# Sheet1.net
KiCad netlist of a schematic drawn in Altium Designer
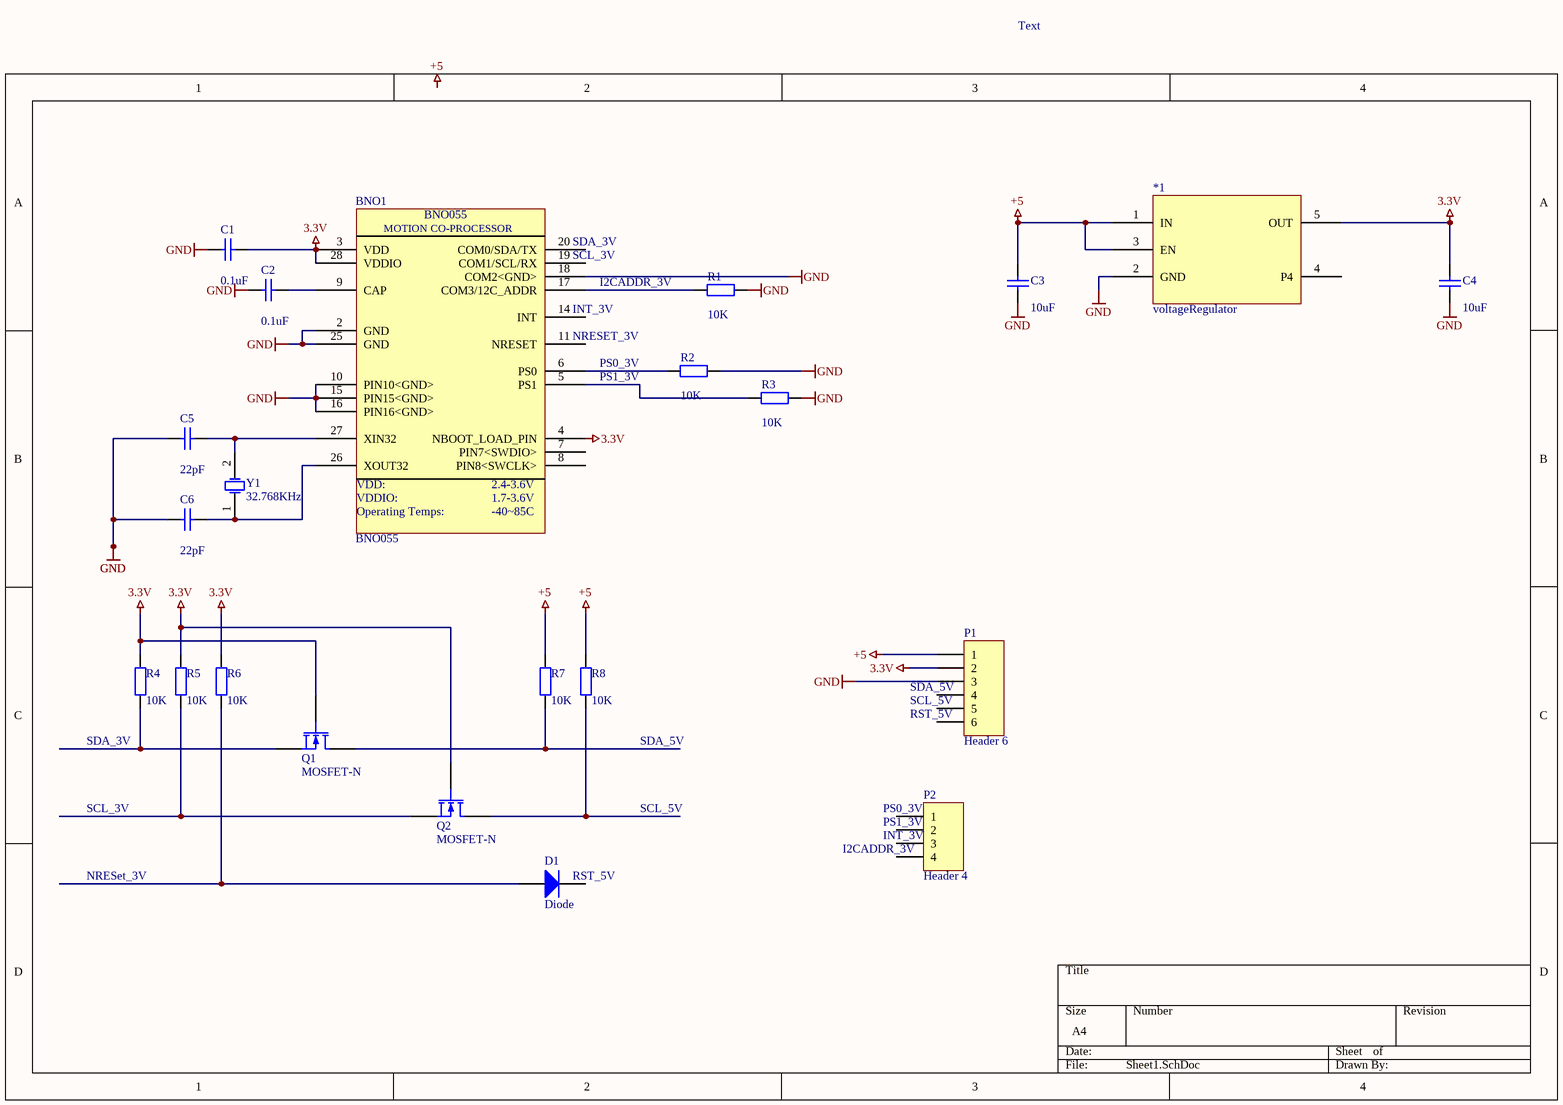
[diagram p0: Sheet1.SchDoc]

(export (version "E")
  (design (tool "Eeschema 10.0.6"))
  (components
    (comp (ref "*1")
      (value "voltageRegulator")
      (footprint "SOT95P245X110-5N")
      (libsource (lib "BNO055SCHEMATIC") (part "voltageRegulator"))
    )
    (comp (ref "BNO1")
      (value "BNO055")
      (footprint "SOIC127P980X95_HS-22N")
      (libsource (lib "BNO055SCHEMATIC") (part "BNO055"))
    )
    (comp (ref "C1")
      (value "0.1uF")
      (footprint "RAD-0.3")
      (description "Capacitor")
      (fields (field (name "PUBLISHER") "Altium Limited"))
      (libsource (lib "Miscellaneous Devices") (part "Cap"))
    )
    (comp (ref "C2")
      (value "0.1uF")
      (footprint "RAD-0.3")
      (description "Capacitor")
      (fields (field (name "PUBLISHER") "Altium Limited"))
      (libsource (lib "Miscellaneous Devices") (part "Cap"))
    )
    (comp (ref "C3")
      (value "10uF")
      (footprint "RAD-0.3")
      (description "Capacitor")
      (fields (field (name "PUBLISHER") "Altium Limited"))
      (libsource (lib "Miscellaneous Devices") (part "Cap"))
    )
    (comp (ref "C4")
      (value "10uF")
      (footprint "RAD-0.3")
      (description "Capacitor")
      (fields (field (name "PUBLISHER") "Altium Limited"))
      (libsource (lib "Miscellaneous Devices") (part "Cap"))
    )
    (comp (ref "C5")
      (value "22pF")
      (footprint "RAD-0.3")
      (description "Capacitor")
      (fields (field (name "PUBLISHER") "Altium Limited"))
      (libsource (lib "Miscellaneous Devices") (part "Cap"))
    )
    (comp (ref "C6")
      (value "22pF")
      (footprint "RAD-0.3")
      (description "Capacitor")
      (fields (field (name "PUBLISHER") "Altium Limited"))
      (libsource (lib "Miscellaneous Devices") (part "Cap"))
    )
    (comp (ref "D1")
      (value "Diode")
      (footprint "SMC")
      (description "Default Diode")
      (fields (field (name "PUBLISHER") "Altium Limited"))
      (libsource (lib "Miscellaneous Devices") (part "Diode"))
    )
    (comp (ref "P1")
      (value "Header 6")
      (footprint "HDR1X6")
      (description "Header, 6-Pin")
      (fields (field (name "PUBLISHER") "Altium Limited"))
      (libsource (lib "Miscellaneous Connectors") (part "Header 6"))
    )
    (comp (ref "P2")
      (value "Header 4")
      (footprint "HDR1X4")
      (description "Header, 4-Pin")
      (fields (field (name "PUBLISHER") "Altium Limited"))
      (libsource (lib "Miscellaneous Connectors") (part "Header 4"))
    )
    (comp (ref "Q1")
      (value "MOSFET-N")
      (footprint "E3")
      (description "N-Channel MOSFET")
      (fields (field (name "PUBLISHER") "Altium Limited"))
      (libsource (lib "Miscellaneous Devices") (part "MOSFET-N"))
    )
    (comp (ref "Q2")
      (value "MOSFET-N")
      (footprint "E3")
      (description "N-Channel MOSFET")
      (fields (field (name "PUBLISHER") "Altium Limited"))
      (libsource (lib "Miscellaneous Devices") (part "MOSFET-N"))
    )
    (comp (ref "R1")
      (value "10K")
      (footprint "AXIAL-0.4")
      (description "Resistor")
      (fields (field (name "PUBLISHER") "Altium Limited"))
      (libsource (lib "") (part "Res2_1"))
    )
    (comp (ref "R2")
      (value "10K")
      (footprint "AXIAL-0.4")
      (description "Resistor")
      (fields (field (name "PUBLISHER") "Altium Limited"))
      (libsource (lib "") (part "Res2_1"))
    )
    (comp (ref "R3")
      (value "10K")
      (footprint "AXIAL-0.4")
      (description "Resistor")
      (fields (field (name "PUBLISHER") "Altium Limited"))
      (libsource (lib "") (part "Res2_1"))
    )
    (comp (ref "R4")
      (value "10K")
      (footprint "AXIAL-0.4")
      (description "Resistor")
      (fields (field (name "PUBLISHER") "Altium Limited"))
      (libsource (lib "Miscellaneous Devices") (part "Res2"))
    )
    (comp (ref "R5")
      (value "10K")
      (footprint "AXIAL-0.4")
      (description "Resistor")
      (fields (field (name "PUBLISHER") "Altium Limited"))
      (libsource (lib "Miscellaneous Devices") (part "Res2"))
    )
    (comp (ref "R6")
      (value "10K")
      (footprint "AXIAL-0.4")
      (description "Resistor")
      (fields (field (name "PUBLISHER") "Altium Limited"))
      (libsource (lib "Miscellaneous Devices") (part "Res2"))
    )
    (comp (ref "R7")
      (value "10K")
      (footprint "AXIAL-0.4")
      (description "Resistor")
      (fields (field (name "PUBLISHER") "Altium Limited"))
      (libsource (lib "Miscellaneous Devices") (part "Res2"))
    )
    (comp (ref "R8")
      (value "10K")
      (footprint "AXIAL-0.4")
      (description "Resistor")
      (fields (field (name "PUBLISHER") "Altium Limited"))
      (libsource (lib "Miscellaneous Devices") (part "Res2"))
    )
    (comp (ref "Y1")
      (value "32.768KHz")
      (footprint "R38")
      (description "Crystal Oscillator")
      (fields (field (name "PUBLISHER") "Altium Limited"))
      (libsource (lib "Miscellaneous Devices") (part "XTAL"))
    )
  )
  (nets
    (net (code "1") (name "+5") (class "Default")
      (node (ref "*1") (pin "1") (pinfunction "IN_1") (pintype "passive"))
      (node (ref "*1") (pin "3") (pinfunction "EN_3") (pintype "passive"))
      (node (ref "C3") (pin "2") (pinfunction "2_2") (pintype "passive"))
      (node (ref "P1") (pin "1") (pinfunction "1_1") (pintype "passive"))
      (node (ref "R7") (pin "2") (pinfunction "2_2") (pintype "passive"))
      (node (ref "R8") (pin "2") (pinfunction "2_2") (pintype "passive"))
    )
    (net (code "2") (name "3.3V") (class "Default")
      (node (ref "*1") (pin "5") (pinfunction "OUT_5") (pintype "passive"))
      (node (ref "BNO1") (pin "28") (pinfunction "VDDIO_28") (pintype "passive"))
      (node (ref "BNO1") (pin "3") (pinfunction "VDD_3") (pintype "passive"))
      (node (ref "BNO1") (pin "4") (pinfunction "NBOOT_LOAD_PIN_4") (pintype "passive"))
      (node (ref "C1") (pin "2") (pinfunction "2_2") (pintype "passive"))
      (node (ref "C4") (pin "2") (pinfunction "2_2") (pintype "passive"))
      (node (ref "P1") (pin "2") (pinfunction "2_2") (pintype "passive"))
      (node (ref "Q1") (pin "2") (pinfunction "G_2") (pintype "passive"))
      (node (ref "Q2") (pin "2") (pinfunction "G_2") (pintype "passive"))
      (node (ref "R4") (pin "2") (pinfunction "2_2") (pintype "passive"))
      (node (ref "R5") (pin "2") (pinfunction "2_2") (pintype "passive"))
      (node (ref "R6") (pin "2") (pinfunction "2_2") (pintype "passive"))
    )
    (net (code "3") (name "GND") (class "Default")
      (node (ref "*1") (pin "2") (pinfunction "GND_2") (pintype "passive"))
      (node (ref "BNO1") (pin "10") (pinfunction "PIN10<GND>_10") (pintype "passive"))
      (node (ref "BNO1") (pin "15") (pinfunction "PIN15<GND>_15") (pintype "passive"))
      (node (ref "BNO1") (pin "16") (pinfunction "PIN16<GND>_16") (pintype "passive"))
      (node (ref "BNO1") (pin "18") (pinfunction "COM2<GND>_18") (pintype "passive"))
      (node (ref "BNO1") (pin "2") (pinfunction "GND_2") (pintype "passive"))
      (node (ref "BNO1") (pin "25") (pinfunction "GND_25") (pintype "passive"))
      (node (ref "C1") (pin "1") (pinfunction "1_1") (pintype "passive"))
      (node (ref "C2") (pin "1") (pinfunction "1_1") (pintype "passive"))
      (node (ref "C3") (pin "1") (pinfunction "1_1") (pintype "passive"))
      (node (ref "C4") (pin "1") (pinfunction "1_1") (pintype "passive"))
      (node (ref "C5") (pin "1") (pinfunction "1_1") (pintype "passive"))
      (node (ref "C6") (pin "1") (pinfunction "1_1") (pintype "passive"))
      (node (ref "P1") (pin "3") (pinfunction "3_3") (pintype "passive"))
      (node (ref "R1") (pin "1") (pinfunction "1_1") (pintype "passive"))
      (node (ref "R2") (pin "1") (pinfunction "1_1") (pintype "passive"))
      (node (ref "R3") (pin "1") (pinfunction "1_1") (pintype "passive"))
    )
    (net (code "4") (name "Net-(BNO1-CAP)") (class "Default")
      (node (ref "BNO1") (pin "9") (pinfunction "CAP_9") (pintype "passive"))
      (node (ref "C2") (pin "2") (pinfunction "2_2") (pintype "passive"))
    )
    (net (code "5") (name "Net-(BNO1-COM3{slash}12C_ADDR)") (class "Default")
      (node (ref "BNO1") (pin "17") (pinfunction "COM3/12C_ADDR_17") (pintype "passive"))
      (node (ref "R1") (pin "2") (pinfunction "2_2") (pintype "passive"))
    )
    (net (code "6") (name "Net-(BNO1-PS0)") (class "Default")
      (node (ref "BNO1") (pin "6") (pinfunction "PS0_6") (pintype "passive"))
      (node (ref "R2") (pin "2") (pinfunction "2_2") (pintype "passive"))
    )
    (net (code "7") (name "Net-(BNO1-PS1)") (class "Default")
      (node (ref "BNO1") (pin "5") (pinfunction "PS1_5") (pintype "passive"))
      (node (ref "R3") (pin "2") (pinfunction "2_2") (pintype "passive"))
    )
    (net (code "8") (name "Net-(BNO1-XIN32)") (class "Default")
      (node (ref "BNO1") (pin "27") (pinfunction "XIN32_27") (pintype "passive"))
      (node (ref "C5") (pin "2") (pinfunction "2_2") (pintype "passive"))
      (node (ref "Y1") (pin "2") (pinfunction "OSC2_2") (pintype "passive"))
    )
    (net (code "9") (name "Net-(BNO1-XOUT32)") (class "Default")
      (node (ref "BNO1") (pin "26") (pinfunction "XOUT32_26") (pintype "passive"))
      (node (ref "C6") (pin "2") (pinfunction "2_2") (pintype "passive"))
      (node (ref "Y1") (pin "1") (pinfunction "OSC1_1") (pintype "passive"))
    )
    (net (code "10") (name "Net-(D1-A)") (class "Default")
      (node (ref "D1") (pin "1") (pinfunction "A_1") (pintype "passive"))
      (node (ref "R6") (pin "1") (pinfunction "1_1") (pintype "passive"))
    )
    (net (code "11") (name "Net-(Q1-D)") (class "Default")
      (node (ref "Q1") (pin "1") (pinfunction "D_1") (pintype "passive"))
      (node (ref "R7") (pin "1") (pinfunction "1_1") (pintype "passive"))
    )
    (net (code "12") (name "Net-(Q1-S)") (class "Default")
      (node (ref "Q1") (pin "3") (pinfunction "S_3") (pintype "passive"))
      (node (ref "R4") (pin "1") (pinfunction "1_1") (pintype "passive"))
    )
    (net (code "13") (name "Net-(Q2-D)") (class "Default")
      (node (ref "Q2") (pin "1") (pinfunction "D_1") (pintype "passive"))
      (node (ref "R8") (pin "1") (pinfunction "1_1") (pintype "passive"))
    )
    (net (code "14") (name "Net-(Q2-S)") (class "Default")
      (node (ref "Q2") (pin "3") (pinfunction "S_3") (pintype "passive"))
      (node (ref "R5") (pin "1") (pinfunction "1_1") (pintype "passive"))
    )
    (net (code "15") (name "unconnected-(*1-P4-Pad4)") (class "Default")
      (node (ref "*1") (pin "4") (pinfunction "P4_4") (pintype "passive"))
    )
    (net (code "16") (name "unconnected-(BNO1-COM0{slash}SDA{slash}TX-Pad20)") (class "Default")
      (node (ref "BNO1") (pin "20") (pinfunction "COM0/SDA/TX_20") (pintype "passive"))
    )
    (net (code "17") (name "unconnected-(BNO1-COM1{slash}SCL{slash}RX-Pad19)") (class "Default")
      (node (ref "BNO1") (pin "19") (pinfunction "COM1/SCL/RX_19") (pintype "passive"))
    )
    (net (code "18") (name "unconnected-(BNO1-INT-Pad14)") (class "Default")
      (node (ref "BNO1") (pin "14") (pinfunction "INT_14") (pintype "passive"))
    )
    (net (code "19") (name "unconnected-(BNO1-NRESET-Pad11)") (class "Default")
      (node (ref "BNO1") (pin "11") (pinfunction "NRESET_11") (pintype "passive"))
    )
    (net (code "20") (name "unconnected-(BNO1-PIN7<SWDIO>-Pad7)") (class "Default")
      (node (ref "BNO1") (pin "7") (pinfunction "PIN7<SWDIO>_7") (pintype "passive"))
    )
    (net (code "21") (name "unconnected-(BNO1-PIN8<SWCLK>-Pad8)") (class "Default")
      (node (ref "BNO1") (pin "8") (pinfunction "PIN8<SWCLK>_8") (pintype "passive"))
    )
    (net (code "22") (name "unconnected-(D1-K-Pad2)") (class "Default")
      (node (ref "D1") (pin "2") (pinfunction "K_2") (pintype "passive"))
    )
    (net (code "23") (name "unconnected-(P1-Pad4)") (class "Default")
      (node (ref "P1") (pin "4") (pinfunction "4_4") (pintype "passive"))
    )
    (net (code "24") (name "unconnected-(P1-Pad5)") (class "Default")
      (node (ref "P1") (pin "5") (pinfunction "5_5") (pintype "passive"))
    )
    (net (code "25") (name "unconnected-(P1-Pad6)") (class "Default")
      (node (ref "P1") (pin "6") (pinfunction "6_6") (pintype "passive"))
    )
    (net (code "26") (name "unconnected-(P2-Pad1)") (class "Default")
      (node (ref "P2") (pin "1") (pinfunction "1_1") (pintype "passive"))
    )
    (net (code "27") (name "unconnected-(P2-Pad2)") (class "Default")
      (node (ref "P2") (pin "2") (pinfunction "2_2") (pintype "passive"))
    )
    (net (code "28") (name "unconnected-(P2-Pad3)") (class "Default")
      (node (ref "P2") (pin "3") (pinfunction "3_3") (pintype "passive"))
    )
    (net (code "29") (name "unconnected-(P2-Pad4)") (class "Default")
      (node (ref "P2") (pin "4") (pinfunction "4_4") (pintype "passive"))
    )
  )
)
